# 60V_Ind.net
KiCad netlist of a schematic drawn in Altium Designer
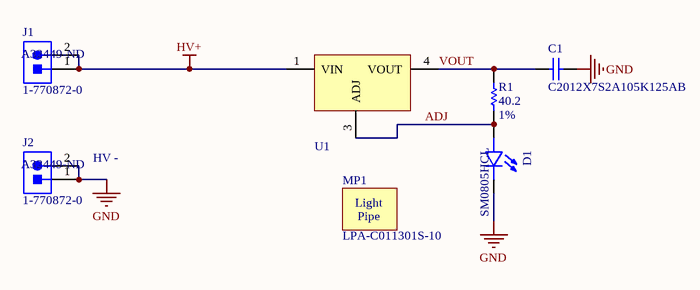
[diagram p0: 60V_Ind.SchDoc]

(export (version "E")
  (design (tool "Eeschema 10.0.6"))
  (components
    (comp (ref "C1")
      (value "C2012X7S2A105K125AB")
      (footprint "CAPC2013X145X20ML20")
      (description "Chip Capacitor, 1 uF, +/- 10%, 100 V, -55 to 125 degC, 0805 (2012 Metric), RoHS, Tape and Reel")
      (fields
        (field (name "PCN PART NUMBER") "MLCCPartNumberChange30/Nov/2012")
        (field (name "MANUFACTURER") "TDK")
      )
      (libsource (lib "Altium Content Vault") (part "CAP-NP-2"))
    )
    (comp (ref "D1")
      (value "SM0805HCL")
      (footprint "LEDC2012X135N_SM0805UGC(Primary)")
      (description "Red 631nm LED Indication - Discrete 1.9V 0805 (2012 Metric)")
      (libsource (lib "60V_Ind") (part "SM0805HCL"))
    )
    (comp (ref "J1")
      (value "1-770872-0")
      (footprint "CON2_1X2_P163_VM")
      (description "Connector Header Through Hole 2 position 0.163\" (4.14mm)")
      (fields
        (field (name "SUPPLIER PART NUMBER 1") "A32449-ND")
        (field (name "COPYRIGHT") "Copyright (C) 2018 Accelerated Designs. All rights reserved")
      )
      (libsource (lib "60V_Ind") (part "1-770872-0"))
    )
    (comp (ref "J2")
      (value "1-770872-0")
      (footprint "CON2_1X2_P163_VM")
      (description "Connector Header Through Hole 2 position 0.163\" (4.14mm)")
      (fields
        (field (name "SUPPLIER PART NUMBER 1") "A32449-ND")
        (field (name "COPYRIGHT") "Copyright (C) 2018 Accelerated Designs. All rights reserved")
      )
      (libsource (lib "60V_Ind") (part "1-770872-0"))
    )
    (comp (ref "MP1")
      (value "LPA-C011301S-10")
      (footprint "LPA-C011301S-10")
      (description "Light Pipe Single Clear Rigid Round with Flat Top, 3mm Board Mount, Press Fit")
      (libsource (lib "60V_Ind") (part "LPA-C011301S-10"))
    )
    (comp (ref "R1")
      (value "40.2 Ohms")
      (footprint "0805_RES")
      (description "Resistor Surface Mount, 40.2 Ohms, 0805 Footprint, 1% Tolerance 0.125W")
      (fields
        (field (name "VAL") "40.2")
        (field (name "TOL") "1%")
        (field (name "MANUFACTURER") "Various")
        (field (name "TOLERANCE") "1%")
      )
      (libsource (lib "Passive Components") (part "res"))
    )
    (comp (ref "U1")
      (value "LR8K4-G")
      (footprint "Microchip_C04-189_MFG")
      (description "Linear Voltage Regulator IC Positive Adjustable 1 Output  10mA TO-252, (D-Pak)")
      (libsource (lib "60V_Ind") (part "LR8K4-G"))
    )
  )
  (nets
    (net (code "1") (name "/ADJ") (class "Default")
      (node (ref "D1") (pin "A") (pinfunction "A_A") (pintype "passive"))
      (node (ref "R1") (pin "1") (pinfunction "1_1") (pintype "passive"))
      (node (ref "U1") (pin "3") (pinfunction "ADJ_3") (pintype "passive"))
    )
    (net (code "2") (name "/VOUT") (class "Default")
      (node (ref "C1") (pin "1") (pinfunction "1_1") (pintype "passive"))
      (node (ref "R1") (pin "2") (pinfunction "2_2") (pintype "passive"))
      (node (ref "U1") (pin "4") (pinfunction "VOUT_4") (pintype "power_in"))
    )
    (net (code "3") (name "GND") (class "Default")
      (node (ref "C1") (pin "2") (pinfunction "2_2") (pintype "passive"))
      (node (ref "D1") (pin "C") (pinfunction "C_C") (pintype "passive"))
      (node (ref "J2") (pin "1") (pinfunction "1_1") (pintype "passive"))
      (node (ref "J2") (pin "2") (pinfunction "2_2") (pintype "passive"))
    )
    (net (code "4") (name "HV+") (class "Default")
      (node (ref "J1") (pin "1") (pinfunction "1_1") (pintype "passive"))
      (node (ref "J1") (pin "2") (pinfunction "2_2") (pintype "passive"))
      (node (ref "U1") (pin "1") (pinfunction "VIN_1") (pintype "power_in"))
    )
  )
)
